# ESC-Beta.net
KiCad netlist of a schematic drawn in EAGLE
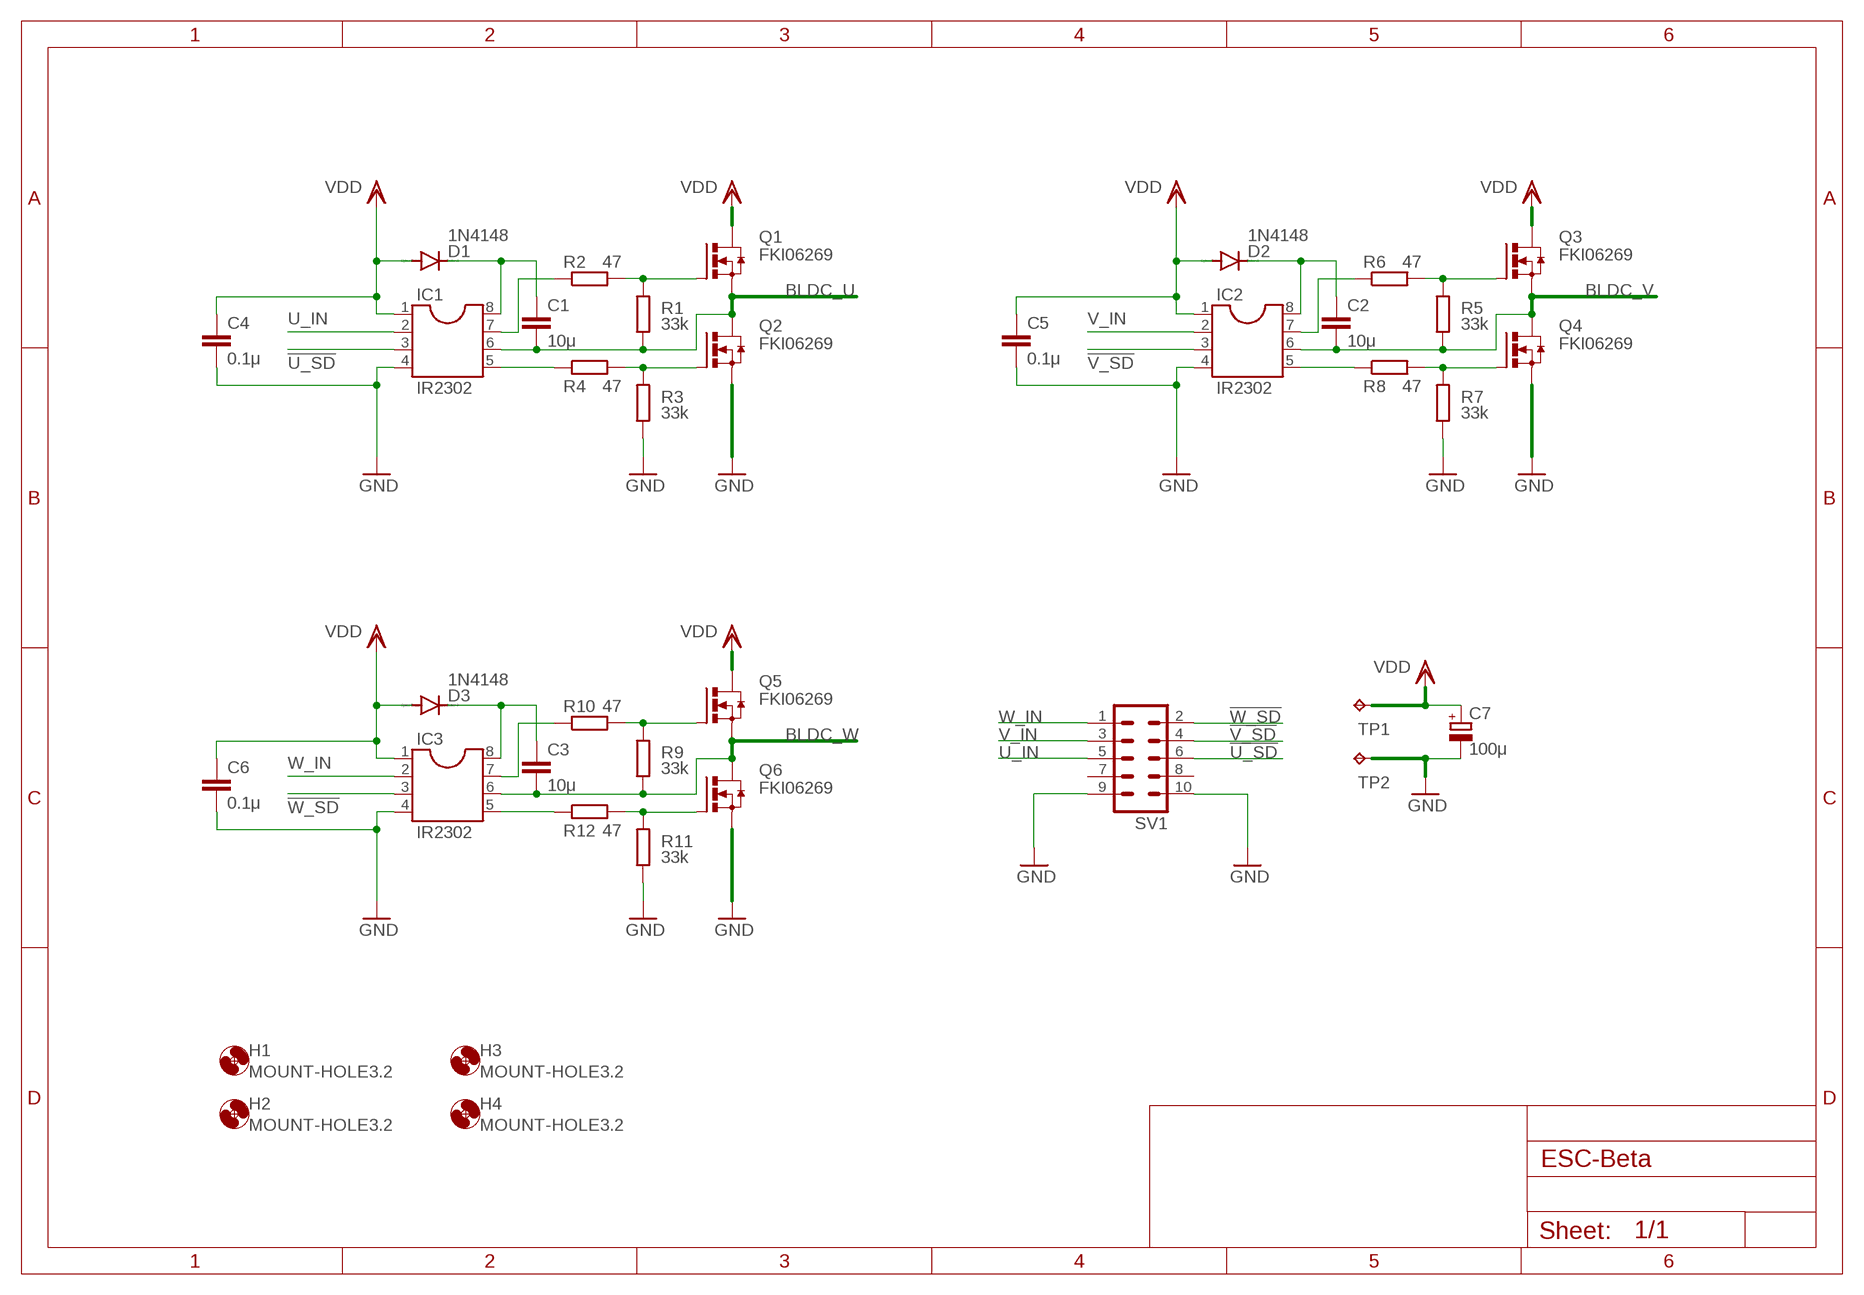
[diagram p0: schematic, sheet 1]

(export (version "E")
  (design (tool "Eeschema 10.0.6"))
  (components
    (comp (ref "C1")
      (value "10μ")
      (footprint "eagle-import:C050-024X044")
      (libsource (lib "eagle-import") (part "C-EU050-024X044"))
    )
    (comp (ref "C2")
      (value "10μ")
      (footprint "eagle-import:C050-024X044")
      (libsource (lib "eagle-import") (part "C-EU050-024X044"))
    )
    (comp (ref "C3")
      (value "10μ")
      (footprint "eagle-import:C050-024X044")
      (libsource (lib "eagle-import") (part "C-EU050-024X044"))
    )
    (comp (ref "C4")
      (value "0.1μ")
      (footprint "eagle-import:C050-024X044")
      (libsource (lib "eagle-import") (part "C-EU050-024X044"))
    )
    (comp (ref "C5")
      (value "0.1μ")
      (footprint "eagle-import:C050-024X044")
      (libsource (lib "eagle-import") (part "C-EU050-024X044"))
    )
    (comp (ref "C6")
      (value "0.1μ")
      (footprint "eagle-import:C050-024X044")
      (libsource (lib "eagle-import") (part "C-EU050-024X044"))
    )
    (comp (ref "C7")
      (value "100μ")
      (footprint "eagle-import:E5-8,5")
      (libsource (lib "eagle-import") (part "CPOL-EUE5-8.5"))
    )
    (comp (ref "D1")
      (value "1N4148")
      (footprint "eagle-import:DO35-7")
      (libsource (lib "eagle-import") (part "1N4148DO35-7"))
    )
    (comp (ref "D2")
      (value "1N4148")
      (footprint "eagle-import:DO35-7")
      (libsource (lib "eagle-import") (part "1N4148DO35-7"))
    )
    (comp (ref "D3")
      (value "1N4148")
      (footprint "eagle-import:DO35-7")
      (libsource (lib "eagle-import") (part "1N4148DO35-7"))
    )
    (comp (ref "H1")
      (value "MOUNT-HOLE3.2")
      (footprint "eagle-import:3,2")
      (libsource (lib "eagle-import") (part "MOUNT-HOLE3.2"))
    )
    (comp (ref "H2")
      (value "MOUNT-HOLE3.2")
      (footprint "eagle-import:3,2")
      (libsource (lib "eagle-import") (part "MOUNT-HOLE3.2"))
    )
    (comp (ref "H3")
      (value "MOUNT-HOLE3.2")
      (footprint "eagle-import:3,2")
      (libsource (lib "eagle-import") (part "MOUNT-HOLE3.2"))
    )
    (comp (ref "H4")
      (value "MOUNT-HOLE3.2")
      (footprint "eagle-import:3,2")
      (libsource (lib "eagle-import") (part "MOUNT-HOLE3.2"))
    )
    (comp (ref "IC1")
      (value "IR2302")
      (footprint "eagle-import:SOCKET-08")
      (libsource (lib "eagle-import") (part "DIL8S"))
    )
    (comp (ref "IC2")
      (value "IR2302")
      (footprint "eagle-import:SOCKET-08")
      (libsource (lib "eagle-import") (part "DIL8S"))
    )
    (comp (ref "IC3")
      (value "IR2302")
      (footprint "eagle-import:SOCKET-08")
      (libsource (lib "eagle-import") (part "DIL8S"))
    )
    (comp (ref "Q1")
      (value "FKI06269")
      (footprint "eagle-import:TO220BH")
      (libsource (lib "eagle-import") (part "IRF3704-H"))
    )
    (comp (ref "Q2")
      (value "FKI06269")
      (footprint "eagle-import:TO220BH")
      (libsource (lib "eagle-import") (part "IRF3704-H"))
    )
    (comp (ref "Q3")
      (value "FKI06269")
      (footprint "eagle-import:TO220BH")
      (libsource (lib "eagle-import") (part "IRF3704-H"))
    )
    (comp (ref "Q4")
      (value "FKI06269")
      (footprint "eagle-import:TO220BH")
      (libsource (lib "eagle-import") (part "IRF3704-H"))
    )
    (comp (ref "Q5")
      (value "FKI06269")
      (footprint "eagle-import:TO220BH")
      (libsource (lib "eagle-import") (part "IRF3704-H"))
    )
    (comp (ref "Q6")
      (value "FKI06269")
      (footprint "eagle-import:TO220BH")
      (libsource (lib "eagle-import") (part "IRF3704-H"))
    )
    (comp (ref "R1")
      (value "33k")
      (footprint "eagle-import:0207_10")
      (libsource (lib "eagle-import") (part "R-EU_0207/10"))
    )
    (comp (ref "R2")
      (value "47")
      (footprint "eagle-import:0207_10")
      (libsource (lib "eagle-import") (part "R-EU_0207/10"))
    )
    (comp (ref "R3")
      (value "33k")
      (footprint "eagle-import:0207_10")
      (libsource (lib "eagle-import") (part "R-EU_0207/10"))
    )
    (comp (ref "R4")
      (value "47")
      (footprint "eagle-import:0207_10")
      (libsource (lib "eagle-import") (part "R-EU_0207/10"))
    )
    (comp (ref "R5")
      (value "33k")
      (footprint "eagle-import:0207_10")
      (libsource (lib "eagle-import") (part "R-EU_0207/10"))
    )
    (comp (ref "R6")
      (value "47")
      (footprint "eagle-import:0207_10")
      (libsource (lib "eagle-import") (part "R-EU_0207/10"))
    )
    (comp (ref "R7")
      (value "33k")
      (footprint "eagle-import:0207_10")
      (libsource (lib "eagle-import") (part "R-EU_0207/10"))
    )
    (comp (ref "R8")
      (value "47")
      (footprint "eagle-import:0207_10")
      (libsource (lib "eagle-import") (part "R-EU_0207/10"))
    )
    (comp (ref "R9")
      (value "33k")
      (footprint "eagle-import:0207_10")
      (libsource (lib "eagle-import") (part "R-EU_0207/10"))
    )
    (comp (ref "R10")
      (value "47")
      (footprint "eagle-import:0207_10")
      (libsource (lib "eagle-import") (part "R-EU_0207/10"))
    )
    (comp (ref "R11")
      (value "33k")
      (footprint "eagle-import:0207_10")
      (libsource (lib "eagle-import") (part "R-EU_0207/10"))
    )
    (comp (ref "R12")
      (value "47")
      (footprint "eagle-import:0207_10")
      (libsource (lib "eagle-import") (part "R-EU_0207/10"))
    )
    (comp (ref "SV1")
      (value "ML10")
      (footprint "eagle-import:ML10")
      (libsource (lib "eagle-import") (part "ML10"))
    )
    (comp (ref "TP1")
      (value "TPPAD1-20")
      (footprint "eagle-import:P1-20")
      (libsource (lib "eagle-import") (part "TPPAD1-20"))
    )
    (comp (ref "TP2")
      (value "TPPAD1-20")
      (footprint "eagle-import:P1-20")
      (libsource (lib "eagle-import") (part "TPPAD1-20"))
    )
  )
  (nets
    (net (code "1") (name "/BLDC_U") (class "Default")
      (node (ref "C1") (pin "2") (pinfunction "2_2") (pintype "passive"))
      (node (ref "IC1") (pin "6") (pinfunction "6_6") (pintype "passive"))
      (node (ref "Q1") (pin "S") (pinfunction "S_S") (pintype "passive"))
      (node (ref "Q2") (pin "D") (pinfunction "D_D") (pintype "passive"))
      (node (ref "R1") (pin "1") (pinfunction "1_1") (pintype "passive"))
    )
    (net (code "2") (name "/BLDC_V") (class "Default")
      (node (ref "C2") (pin "2") (pinfunction "2_2") (pintype "passive"))
      (node (ref "IC2") (pin "6") (pinfunction "6_6") (pintype "passive"))
      (node (ref "Q3") (pin "S") (pinfunction "S_S") (pintype "passive"))
      (node (ref "Q4") (pin "D") (pinfunction "D_D") (pintype "passive"))
      (node (ref "R5") (pin "1") (pinfunction "1_1") (pintype "passive"))
    )
    (net (code "3") (name "/BLDC_W") (class "Default")
      (node (ref "C3") (pin "2") (pinfunction "2_2") (pintype "passive"))
      (node (ref "IC3") (pin "6") (pinfunction "6_6") (pintype "passive"))
      (node (ref "Q5") (pin "S") (pinfunction "S_S") (pintype "passive"))
      (node (ref "Q6") (pin "D") (pinfunction "D_D") (pintype "passive"))
      (node (ref "R9") (pin "1") (pinfunction "1_1") (pintype "passive"))
    )
    (net (code "4") (name "/U_IN") (class "Default")
      (node (ref "IC1") (pin "2") (pinfunction "2_2") (pintype "passive"))
      (node (ref "SV1") (pin "5") (pinfunction "5_5") (pintype "passive"))
    )
    (net (code "5") (name "/V_IN") (class "Default")
      (node (ref "IC2") (pin "2") (pinfunction "2_2") (pintype "passive"))
      (node (ref "SV1") (pin "3") (pinfunction "3_3") (pintype "passive"))
    )
    (net (code "6") (name "/W_IN") (class "Default")
      (node (ref "IC3") (pin "2") (pinfunction "2_2") (pintype "passive"))
      (node (ref "SV1") (pin "1") (pinfunction "1_1") (pintype "passive"))
    )
    (net (code "7") (name "/~{U_SD}") (class "Default")
      (node (ref "IC1") (pin "3") (pinfunction "3_3") (pintype "passive"))
      (node (ref "SV1") (pin "6") (pinfunction "6_6") (pintype "passive"))
    )
    (net (code "8") (name "/~{V_SD}") (class "Default")
      (node (ref "IC2") (pin "3") (pinfunction "3_3") (pintype "passive"))
      (node (ref "SV1") (pin "4") (pinfunction "4_4") (pintype "passive"))
    )
    (net (code "9") (name "/~{W_SD}") (class "Default")
      (node (ref "IC3") (pin "3") (pinfunction "3_3") (pintype "passive"))
      (node (ref "SV1") (pin "2") (pinfunction "2_2") (pintype "passive"))
    )
    (net (code "10") (name "GND") (class "Default")
      (node (ref "C4") (pin "2") (pinfunction "2_2") (pintype "passive"))
      (node (ref "C5") (pin "2") (pinfunction "2_2") (pintype "passive"))
      (node (ref "C6") (pin "2") (pinfunction "2_2") (pintype "passive"))
      (node (ref "C7") (pin "-") (pinfunction "-_-") (pintype "passive"))
      (node (ref "IC1") (pin "4") (pinfunction "4_4") (pintype "passive"))
      (node (ref "IC2") (pin "4") (pinfunction "4_4") (pintype "passive"))
      (node (ref "IC3") (pin "4") (pinfunction "4_4") (pintype "passive"))
      (node (ref "Q2") (pin "S") (pinfunction "S_S") (pintype "passive"))
      (node (ref "Q4") (pin "S") (pinfunction "S_S") (pintype "passive"))
      (node (ref "Q6") (pin "S") (pinfunction "S_S") (pintype "passive"))
      (node (ref "R11") (pin "1") (pinfunction "1_1") (pintype "passive"))
      (node (ref "R3") (pin "1") (pinfunction "1_1") (pintype "passive"))
      (node (ref "R7") (pin "1") (pinfunction "1_1") (pintype "passive"))
      (node (ref "SV1") (pin "10") (pinfunction "10_10") (pintype "passive"))
      (node (ref "SV1") (pin "9") (pinfunction "9_9") (pintype "passive"))
      (node (ref "TP2") (pin "TP") (pinfunction "TP_TP") (pintype "input"))
    )
    (net (code "11") (name "Net-(C1-Pad1)") (class "Default")
      (node (ref "C1") (pin "1") (pinfunction "1_1") (pintype "passive"))
      (node (ref "D1") (pin "C") (pinfunction "C_C") (pintype "passive"))
      (node (ref "IC1") (pin "8") (pinfunction "8_8") (pintype "passive"))
    )
    (net (code "12") (name "Net-(C2-Pad1)") (class "Default")
      (node (ref "C2") (pin "1") (pinfunction "1_1") (pintype "passive"))
      (node (ref "D2") (pin "C") (pinfunction "C_C") (pintype "passive"))
      (node (ref "IC2") (pin "8") (pinfunction "8_8") (pintype "passive"))
    )
    (net (code "13") (name "Net-(C3-Pad1)") (class "Default")
      (node (ref "C3") (pin "1") (pinfunction "1_1") (pintype "passive"))
      (node (ref "D3") (pin "C") (pinfunction "C_C") (pintype "passive"))
      (node (ref "IC3") (pin "8") (pinfunction "8_8") (pintype "passive"))
    )
    (net (code "14") (name "Net-(IC1-Pad5)") (class "Default")
      (node (ref "IC1") (pin "5") (pinfunction "5_5") (pintype "passive"))
      (node (ref "R4") (pin "1") (pinfunction "1_1") (pintype "passive"))
    )
    (net (code "15") (name "Net-(IC1-Pad7)") (class "Default")
      (node (ref "IC1") (pin "7") (pinfunction "7_7") (pintype "passive"))
      (node (ref "R2") (pin "1") (pinfunction "1_1") (pintype "passive"))
    )
    (net (code "16") (name "Net-(IC2-Pad5)") (class "Default")
      (node (ref "IC2") (pin "5") (pinfunction "5_5") (pintype "passive"))
      (node (ref "R8") (pin "1") (pinfunction "1_1") (pintype "passive"))
    )
    (net (code "17") (name "Net-(IC2-Pad7)") (class "Default")
      (node (ref "IC2") (pin "7") (pinfunction "7_7") (pintype "passive"))
      (node (ref "R6") (pin "1") (pinfunction "1_1") (pintype "passive"))
    )
    (net (code "18") (name "Net-(IC3-Pad5)") (class "Default")
      (node (ref "IC3") (pin "5") (pinfunction "5_5") (pintype "passive"))
      (node (ref "R12") (pin "1") (pinfunction "1_1") (pintype "passive"))
    )
    (net (code "19") (name "Net-(IC3-Pad7)") (class "Default")
      (node (ref "IC3") (pin "7") (pinfunction "7_7") (pintype "passive"))
      (node (ref "R10") (pin "1") (pinfunction "1_1") (pintype "passive"))
    )
    (net (code "20") (name "Net-(Q1-PadG)") (class "Default")
      (node (ref "Q1") (pin "G") (pinfunction "G_G") (pintype "passive"))
      (node (ref "R1") (pin "2") (pinfunction "2_2") (pintype "passive"))
      (node (ref "R2") (pin "2") (pinfunction "2_2") (pintype "passive"))
    )
    (net (code "21") (name "Net-(Q2-PadG)") (class "Default")
      (node (ref "Q2") (pin "G") (pinfunction "G_G") (pintype "passive"))
      (node (ref "R3") (pin "2") (pinfunction "2_2") (pintype "passive"))
      (node (ref "R4") (pin "2") (pinfunction "2_2") (pintype "passive"))
    )
    (net (code "22") (name "Net-(Q3-PadG)") (class "Default")
      (node (ref "Q3") (pin "G") (pinfunction "G_G") (pintype "passive"))
      (node (ref "R5") (pin "2") (pinfunction "2_2") (pintype "passive"))
      (node (ref "R6") (pin "2") (pinfunction "2_2") (pintype "passive"))
    )
    (net (code "23") (name "Net-(Q4-PadG)") (class "Default")
      (node (ref "Q4") (pin "G") (pinfunction "G_G") (pintype "passive"))
      (node (ref "R7") (pin "2") (pinfunction "2_2") (pintype "passive"))
      (node (ref "R8") (pin "2") (pinfunction "2_2") (pintype "passive"))
    )
    (net (code "24") (name "Net-(Q5-PadG)") (class "Default")
      (node (ref "Q5") (pin "G") (pinfunction "G_G") (pintype "passive"))
      (node (ref "R10") (pin "2") (pinfunction "2_2") (pintype "passive"))
      (node (ref "R9") (pin "2") (pinfunction "2_2") (pintype "passive"))
    )
    (net (code "25") (name "Net-(Q6-PadG)") (class "Default")
      (node (ref "Q6") (pin "G") (pinfunction "G_G") (pintype "passive"))
      (node (ref "R11") (pin "2") (pinfunction "2_2") (pintype "passive"))
      (node (ref "R12") (pin "2") (pinfunction "2_2") (pintype "passive"))
    )
    (net (code "26") (name "VDD") (class "Default")
      (node (ref "C4") (pin "1") (pinfunction "1_1") (pintype "passive"))
      (node (ref "C5") (pin "1") (pinfunction "1_1") (pintype "passive"))
      (node (ref "C6") (pin "1") (pinfunction "1_1") (pintype "passive"))
      (node (ref "C7") (pin "+") (pinfunction "+_+") (pintype "passive"))
      (node (ref "D1") (pin "A") (pinfunction "A_A") (pintype "passive"))
      (node (ref "D2") (pin "A") (pinfunction "A_A") (pintype "passive"))
      (node (ref "D3") (pin "A") (pinfunction "A_A") (pintype "passive"))
      (node (ref "IC1") (pin "1") (pinfunction "1_1") (pintype "passive"))
      (node (ref "IC2") (pin "1") (pinfunction "1_1") (pintype "passive"))
      (node (ref "IC3") (pin "1") (pinfunction "1_1") (pintype "passive"))
      (node (ref "Q1") (pin "D") (pinfunction "D_D") (pintype "passive"))
      (node (ref "Q3") (pin "D") (pinfunction "D_D") (pintype "passive"))
      (node (ref "Q5") (pin "D") (pinfunction "D_D") (pintype "passive"))
      (node (ref "TP1") (pin "TP") (pinfunction "TP_TP") (pintype "input"))
    )
    (net (code "27") (name "unconnected-(SV1-Pad7)") (class "Default")
      (node (ref "SV1") (pin "7") (pinfunction "7_7") (pintype "passive"))
    )
    (net (code "28") (name "unconnected-(SV1-Pad8)") (class "Default")
      (node (ref "SV1") (pin "8") (pinfunction "8_8") (pintype "passive"))
    )
  )
)
